# 2.net
KiCad netlist of a schematic drawn in Altium Designer
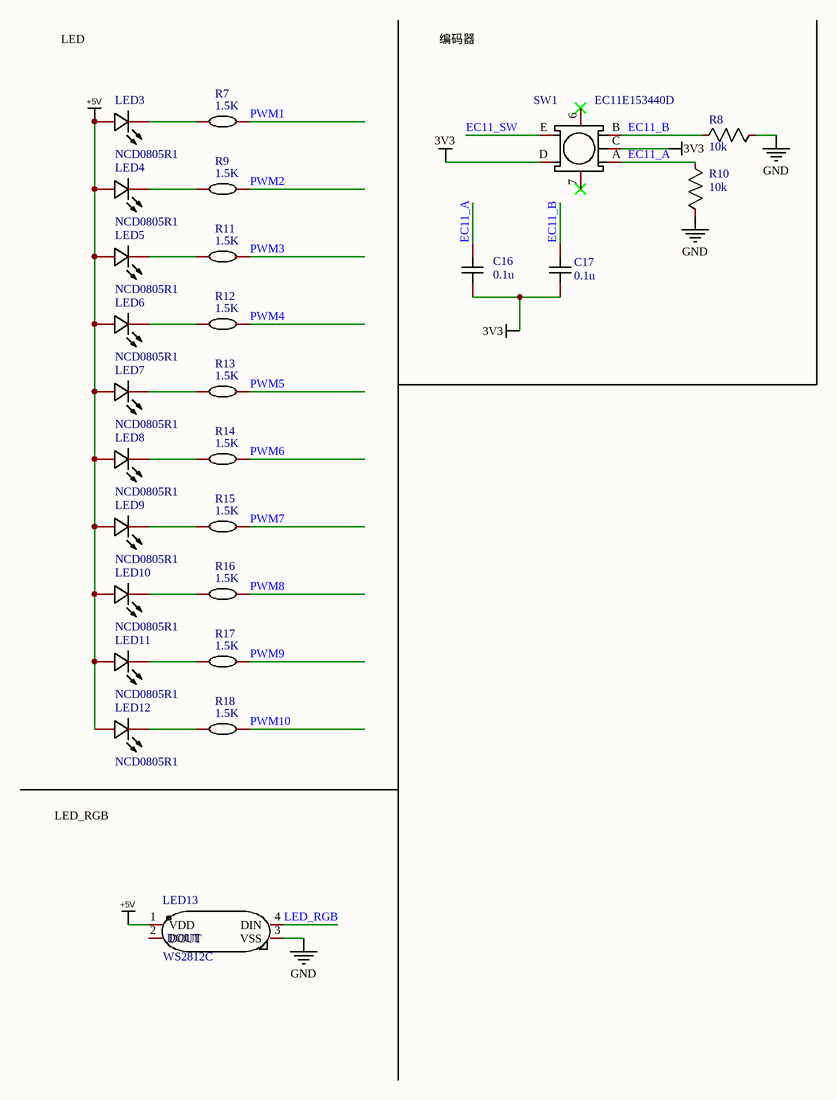
[diagram p0: 2_外围电路.schdoc]

(export (version "E")
  (design (tool "Eeschema 10.0.6"))
  (components
    (comp (ref "C16")
      (value "0.1u")
      (footprint "C0805")
      (fields (field (name "NAME") "0.1u"))
      (libsource (lib "altium-import") (part "root_1_0.1u_"))
    )
    (comp (ref "C17")
      (value "0.1u")
      (footprint "C0805")
      (fields (field (name "NAME") "0.1u"))
      (libsource (lib "altium-import") (part "root_1_0.1u_"))
    )
    (comp (ref "LED3")
      (value "NCD0805R1")
      (footprint "LED0805-RD_RED")
      (description "发光颜色:红灯;")
      (fields (field (name "NAME") "NCD0805R1") (field (name "MANUFACTURER") "国星光电"))
      (libsource (lib "altium-import") (part "root_2_NCD0805R1_"))
    )
    (comp (ref "LED4")
      (value "NCD0805R1")
      (footprint "LED0805-RD_RED")
      (description "发光颜色:红灯;")
      (fields (field (name "NAME") "NCD0805R1") (field (name "MANUFACTURER") "国星光电"))
      (libsource (lib "altium-import") (part "root_2_NCD0805R1_"))
    )
    (comp (ref "LED5")
      (value "NCD0805R1")
      (footprint "LED0805-RD_RED")
      (description "发光颜色:红灯;")
      (fields (field (name "NAME") "NCD0805R1") (field (name "MANUFACTURER") "国星光电"))
      (libsource (lib "altium-import") (part "root_2_NCD0805R1_"))
    )
    (comp (ref "LED6")
      (value "NCD0805R1")
      (footprint "LED0805-RD_RED")
      (description "发光颜色:红灯;")
      (fields (field (name "NAME") "NCD0805R1") (field (name "MANUFACTURER") "国星光电"))
      (libsource (lib "altium-import") (part "root_2_NCD0805R1_"))
    )
    (comp (ref "LED7")
      (value "NCD0805R1")
      (footprint "LED0805-RD_RED")
      (description "发光颜色:红灯;")
      (fields (field (name "NAME") "NCD0805R1") (field (name "MANUFACTURER") "国星光电"))
      (libsource (lib "altium-import") (part "root_2_NCD0805R1_"))
    )
    (comp (ref "LED8")
      (value "NCD0805R1")
      (footprint "LED0805-RD_RED")
      (description "发光颜色:红灯;")
      (fields (field (name "NAME") "NCD0805R1") (field (name "MANUFACTURER") "国星光电"))
      (libsource (lib "altium-import") (part "root_2_NCD0805R1_"))
    )
    (comp (ref "LED9")
      (value "NCD0805R1")
      (footprint "LED0805-RD_RED")
      (description "发光颜色:红灯;")
      (fields (field (name "NAME") "NCD0805R1") (field (name "MANUFACTURER") "国星光电"))
      (libsource (lib "altium-import") (part "root_2_NCD0805R1_"))
    )
    (comp (ref "LED10")
      (value "NCD0805R1")
      (footprint "LED0805-RD_RED")
      (description "发光颜色:红灯;")
      (fields (field (name "NAME") "NCD0805R1") (field (name "MANUFACTURER") "国星光电"))
      (libsource (lib "altium-import") (part "root_2_NCD0805R1_"))
    )
    (comp (ref "LED11")
      (value "NCD0805R1")
      (footprint "LED0805-RD_RED")
      (description "发光颜色:红灯;")
      (fields (field (name "NAME") "NCD0805R1") (field (name "MANUFACTURER") "国星光电"))
      (libsource (lib "altium-import") (part "root_2_NCD0805R1_"))
    )
    (comp (ref "LED12")
      (value "NCD0805R1")
      (footprint "LED0805-RD_RED")
      (description "发光颜色:红灯;")
      (fields (field (name "NAME") "NCD0805R1") (field (name "MANUFACTURER") "国星光电"))
      (libsource (lib "altium-import") (part "root_2_NCD0805R1_"))
    )
    (comp (ref "LED13")
      (value "WS2812C")
      (footprint "LED-SMD_4P-L5.0-W5.0-LS5.4-TL-1")
      (description "发光颜色:RGB三色;")
      (fields
        (field (name "NAME") "WS2812C")
        (field (name "MANUFACTURER") "worldsemi")
        (field (name "NAME_1") "DOUT")
      )
      (libsource (lib "altium-import") (part "root_0_WS2812C_"))
    )
    (comp (ref "R7")
      (value "1.5K")
      (footprint "R0805")
      (fields
        (field (name "NAME") "1.5K")
        (field (name "MANUFACTURER") "YAGEO(国巨)")
        (field (name "MANUFACTURER PART") "AC0805FR-071K5L")
      )
      (libsource (lib "altium-import") (part "root_0_AC0805FR-071K5L_"))
    )
    (comp (ref "R8")
      (value "10k")
      (footprint "R0805")
      (fields (field (name "NAME") "10k"))
      (libsource (lib "altium-import") (part "root_2_10k_"))
    )
    (comp (ref "R9")
      (value "1.5K")
      (footprint "R0805")
      (fields
        (field (name "NAME") "1.5K")
        (field (name "MANUFACTURER") "YAGEO(国巨)")
        (field (name "MANUFACTURER PART") "AC0805FR-071K5L")
      )
      (libsource (lib "altium-import") (part "root_0_AC0805FR-071K5L_"))
    )
    (comp (ref "R10")
      (value "10k")
      (footprint "R0805")
      (fields (field (name "NAME") "10k"))
      (libsource (lib "altium-import") (part "root_3_10k_"))
    )
    (comp (ref "R11")
      (value "1.5K")
      (footprint "R0805")
      (fields
        (field (name "NAME") "1.5K")
        (field (name "MANUFACTURER") "YAGEO(国巨)")
        (field (name "MANUFACTURER PART") "AC0805FR-071K5L")
      )
      (libsource (lib "altium-import") (part "root_0_AC0805FR-071K5L_"))
    )
    (comp (ref "R12")
      (value "1.5K")
      (footprint "R0805")
      (fields
        (field (name "NAME") "1.5K")
        (field (name "MANUFACTURER") "YAGEO(国巨)")
        (field (name "MANUFACTURER PART") "AC0805FR-071K5L")
      )
      (libsource (lib "altium-import") (part "root_0_AC0805FR-071K5L_"))
    )
    (comp (ref "R13")
      (value "1.5K")
      (footprint "R0805")
      (fields
        (field (name "NAME") "1.5K")
        (field (name "MANUFACTURER") "YAGEO(国巨)")
        (field (name "MANUFACTURER PART") "AC0805FR-071K5L")
      )
      (libsource (lib "altium-import") (part "root_0_AC0805FR-071K5L_"))
    )
    (comp (ref "R14")
      (value "1.5K")
      (footprint "R0805")
      (fields
        (field (name "NAME") "1.5K")
        (field (name "MANUFACTURER") "YAGEO(国巨)")
        (field (name "MANUFACTURER PART") "AC0805FR-071K5L")
      )
      (libsource (lib "altium-import") (part "root_0_AC0805FR-071K5L_"))
    )
    (comp (ref "R15")
      (value "1.5K")
      (footprint "R0805")
      (fields
        (field (name "NAME") "1.5K")
        (field (name "MANUFACTURER") "YAGEO(国巨)")
        (field (name "MANUFACTURER PART") "AC0805FR-071K5L")
      )
      (libsource (lib "altium-import") (part "root_0_AC0805FR-071K5L_"))
    )
    (comp (ref "R16")
      (value "1.5K")
      (footprint "R0805")
      (fields
        (field (name "NAME") "1.5K")
        (field (name "MANUFACTURER") "YAGEO(国巨)")
        (field (name "MANUFACTURER PART") "AC0805FR-071K5L")
      )
      (libsource (lib "altium-import") (part "root_0_AC0805FR-071K5L_"))
    )
    (comp (ref "R17")
      (value "1.5K")
      (footprint "R0805")
      (fields
        (field (name "NAME") "1.5K")
        (field (name "MANUFACTURER") "YAGEO(国巨)")
        (field (name "MANUFACTURER PART") "AC0805FR-071K5L")
      )
      (libsource (lib "altium-import") (part "root_0_AC0805FR-071K5L_"))
    )
    (comp (ref "R18")
      (value "1.5K")
      (footprint "R0805")
      (fields
        (field (name "NAME") "1.5K")
        (field (name "MANUFACTURER") "YAGEO(国巨)")
        (field (name "MANUFACTURER PART") "AC0805FR-071K5L")
      )
      (libsource (lib "altium-import") (part "root_0_AC0805FR-071K5L_"))
    )
    (comp (ref "SW1")
      (value "EC11E153440D")
      (footprint "SW-TH_EC11XXXXXXXX")
      (fields (field (name "NAME") "EC11E153440D") (field (name "MANUFACTURER") "ALPSALPINE(阿尔卑斯阿尔派)"))
      (libsource (lib "altium-import") (part "root_1_EC11E153440D_"))
    )
  )
  (nets
    (net (code "1") (name "+5V") (class "Default")
      (node (ref "LED10") (pin "2") (pinfunction "+_2") (pintype "passive"))
      (node (ref "LED11") (pin "2") (pinfunction "+_2") (pintype "passive"))
      (node (ref "LED12") (pin "2") (pinfunction "+_2") (pintype "passive"))
      (node (ref "LED13") (pin "1") (pinfunction "VDD_1") (pintype "passive"))
      (node (ref "LED3") (pin "2") (pinfunction "+_2") (pintype "passive"))
      (node (ref "LED4") (pin "2") (pinfunction "+_2") (pintype "passive"))
      (node (ref "LED5") (pin "2") (pinfunction "+_2") (pintype "passive"))
      (node (ref "LED6") (pin "2") (pinfunction "+_2") (pintype "passive"))
      (node (ref "LED7") (pin "2") (pinfunction "+_2") (pintype "passive"))
      (node (ref "LED8") (pin "2") (pinfunction "+_2") (pintype "passive"))
      (node (ref "LED9") (pin "2") (pinfunction "+_2") (pintype "passive"))
    )
    (net (code "2") (name "/EC11_A") (class "Default")
      (node (ref "C16") (pin "2") (pinfunction "2_2") (pintype "passive"))
      (node (ref "R10") (pin "1") (pinfunction "1_1") (pintype "passive"))
      (node (ref "SW1") (pin "A") (pinfunction "A_A") (pintype "passive"))
    )
    (net (code "3") (name "/EC11_B") (class "Default")
      (node (ref "C17") (pin "2") (pinfunction "2_2") (pintype "passive"))
      (node (ref "R8") (pin "2") (pinfunction "2_2") (pintype "passive"))
      (node (ref "SW1") (pin "B") (pinfunction "B_B") (pintype "passive"))
    )
    (net (code "4") (name "/EC11_SW") (class "Default")
      (node (ref "SW1") (pin "E") (pinfunction "E_E") (pintype "passive"))
    )
    (net (code "5") (name "/LED_RGB") (class "Default")
      (node (ref "LED13") (pin "4") (pinfunction "DIN_4") (pintype "passive"))
    )
    (net (code "6") (name "/PWM1") (class "Default")
      (node (ref "R7") (pin "2") (pinfunction "2_2") (pintype "passive"))
    )
    (net (code "7") (name "/PWM2") (class "Default")
      (node (ref "R9") (pin "2") (pinfunction "2_2") (pintype "passive"))
    )
    (net (code "8") (name "/PWM3") (class "Default")
      (node (ref "R11") (pin "2") (pinfunction "2_2") (pintype "passive"))
    )
    (net (code "9") (name "/PWM4") (class "Default")
      (node (ref "R12") (pin "2") (pinfunction "2_2") (pintype "passive"))
    )
    (net (code "10") (name "/PWM5") (class "Default")
      (node (ref "R13") (pin "2") (pinfunction "2_2") (pintype "passive"))
    )
    (net (code "11") (name "/PWM6") (class "Default")
      (node (ref "R14") (pin "2") (pinfunction "2_2") (pintype "passive"))
    )
    (net (code "12") (name "/PWM7") (class "Default")
      (node (ref "R15") (pin "2") (pinfunction "2_2") (pintype "passive"))
    )
    (net (code "13") (name "/PWM8") (class "Default")
      (node (ref "R16") (pin "2") (pinfunction "2_2") (pintype "passive"))
    )
    (net (code "14") (name "/PWM9") (class "Default")
      (node (ref "R17") (pin "2") (pinfunction "2_2") (pintype "passive"))
    )
    (net (code "15") (name "/PWM10") (class "Default")
      (node (ref "R18") (pin "2") (pinfunction "2_2") (pintype "passive"))
    )
    (net (code "16") (name "3V3") (class "Default")
      (node (ref "C16") (pin "1") (pinfunction "1_1") (pintype "passive"))
      (node (ref "C17") (pin "1") (pinfunction "1_1") (pintype "passive"))
      (node (ref "SW1") (pin "C") (pinfunction "C_C") (pintype "passive"))
      (node (ref "SW1") (pin "D") (pinfunction "D_D") (pintype "passive"))
    )
    (net (code "17") (name "GND") (class "Default")
      (node (ref "LED13") (pin "3") (pinfunction "VSS_3") (pintype "passive"))
      (node (ref "R10") (pin "2") (pinfunction "2_2") (pintype "passive"))
      (node (ref "R8") (pin "1") (pinfunction "1_1") (pintype "passive"))
    )
    (net (code "18") (name "Net-(LED3--)") (class "Default")
      (node (ref "LED3") (pin "1") (pinfunction "-_1") (pintype "passive"))
      (node (ref "R7") (pin "1") (pinfunction "1_1") (pintype "passive"))
    )
    (net (code "19") (name "Net-(LED4--)") (class "Default")
      (node (ref "LED4") (pin "1") (pinfunction "-_1") (pintype "passive"))
      (node (ref "R9") (pin "1") (pinfunction "1_1") (pintype "passive"))
    )
    (net (code "20") (name "Net-(LED5--)") (class "Default")
      (node (ref "LED5") (pin "1") (pinfunction "-_1") (pintype "passive"))
      (node (ref "R11") (pin "1") (pinfunction "1_1") (pintype "passive"))
    )
    (net (code "21") (name "Net-(LED6--)") (class "Default")
      (node (ref "LED6") (pin "1") (pinfunction "-_1") (pintype "passive"))
      (node (ref "R12") (pin "1") (pinfunction "1_1") (pintype "passive"))
    )
    (net (code "22") (name "Net-(LED7--)") (class "Default")
      (node (ref "LED7") (pin "1") (pinfunction "-_1") (pintype "passive"))
      (node (ref "R13") (pin "1") (pinfunction "1_1") (pintype "passive"))
    )
    (net (code "23") (name "Net-(LED8--)") (class "Default")
      (node (ref "LED8") (pin "1") (pinfunction "-_1") (pintype "passive"))
      (node (ref "R14") (pin "1") (pinfunction "1_1") (pintype "passive"))
    )
    (net (code "24") (name "Net-(LED9--)") (class "Default")
      (node (ref "LED9") (pin "1") (pinfunction "-_1") (pintype "passive"))
      (node (ref "R15") (pin "1") (pinfunction "1_1") (pintype "passive"))
    )
    (net (code "25") (name "Net-(LED10--)") (class "Default")
      (node (ref "LED10") (pin "1") (pinfunction "-_1") (pintype "passive"))
      (node (ref "R16") (pin "1") (pinfunction "1_1") (pintype "passive"))
    )
    (net (code "26") (name "Net-(LED11--)") (class "Default")
      (node (ref "LED11") (pin "1") (pinfunction "-_1") (pintype "passive"))
      (node (ref "R17") (pin "1") (pinfunction "1_1") (pintype "passive"))
    )
    (net (code "27") (name "Net-(LED12--)") (class "Default")
      (node (ref "LED12") (pin "1") (pinfunction "-_1") (pintype "passive"))
      (node (ref "R18") (pin "1") (pinfunction "1_1") (pintype "passive"))
    )
    (net (code "28") (name "unconnected-(LED13-DOUT-Pad2)") (class "Default")
      (node (ref "LED13") (pin "2") (pinfunction "DOUT_2") (pintype "passive"))
    )
    (net (code "29") (name "unconnected-(SW1-Pad6)") (class "Default")
      (node (ref "SW1") (pin "6") (pinfunction "6_6") (pintype "passive+no_connect"))
    )
    (net (code "30") (name "unconnected-(SW1-Pad7)") (class "Default")
      (node (ref "SW1") (pin "7") (pinfunction "7_7") (pintype "passive+no_connect"))
    )
  )
)
